# DS2408_2PIO_6S_v2.net
KiCad netlist of a schematic drawn in EAGLE
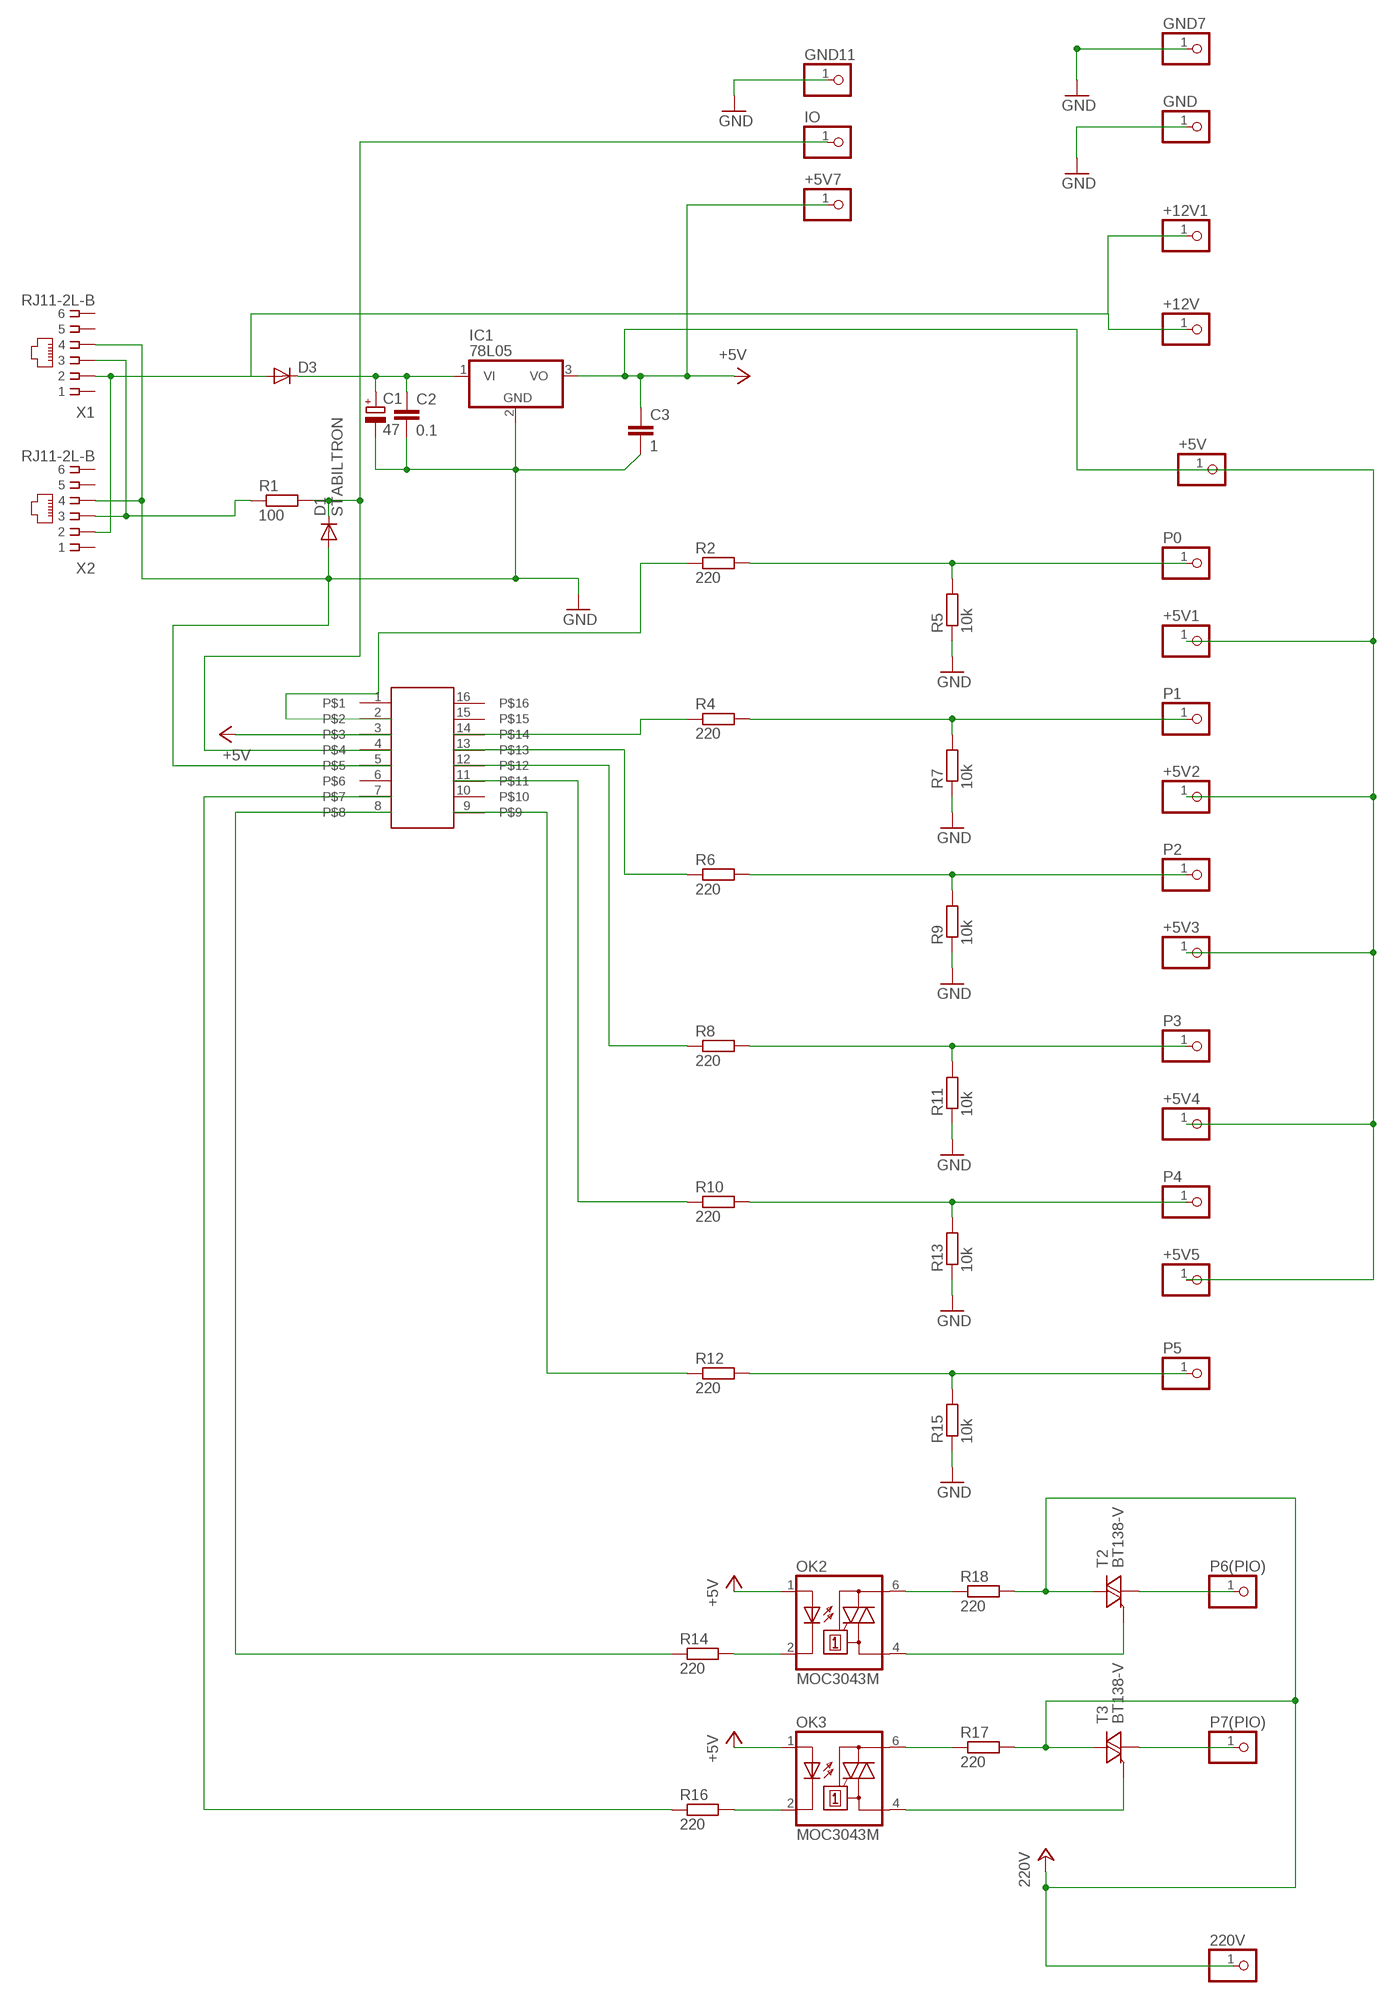
[diagram p0: schematic, sheet 1]

(export (version "E")
  (design (tool "Eeschema 10.0.6"))
  (components
    (comp (ref "+5V")
      (value "PINHD-1X1")
      (footprint "eagle-import:1X01")
      (libsource (lib "eagle-import") (part "PINHD-1X1"))
    )
    (comp (ref "+5V1")
      (value "PINHD-1X1")
      (footprint "eagle-import:1X01")
      (libsource (lib "eagle-import") (part "PINHD-1X1"))
    )
    (comp (ref "+5V2")
      (value "PINHD-1X1")
      (footprint "eagle-import:1X01")
      (libsource (lib "eagle-import") (part "PINHD-1X1"))
    )
    (comp (ref "+5V3")
      (value "PINHD-1X1")
      (footprint "eagle-import:1X01")
      (libsource (lib "eagle-import") (part "PINHD-1X1"))
    )
    (comp (ref "+5V4")
      (value "PINHD-1X1")
      (footprint "eagle-import:1X01")
      (libsource (lib "eagle-import") (part "PINHD-1X1"))
    )
    (comp (ref "+5V5")
      (value "PINHD-1X1")
      (footprint "eagle-import:1X01")
      (libsource (lib "eagle-import") (part "PINHD-1X1"))
    )
    (comp (ref "+5V7")
      (value "PINHD-1X1")
      (footprint "eagle-import:1X01")
      (libsource (lib "eagle-import") (part "PINHD-1X1"))
    )
    (comp (ref "+12V")
      (value "PINHD-1X1")
      (footprint "eagle-import:1X01")
      (libsource (lib "eagle-import") (part "PINHD-1X1"))
    )
    (comp (ref "+12V1")
      (value "PINHD-1X1")
      (footprint "eagle-import:1X01")
      (libsource (lib "eagle-import") (part "PINHD-1X1"))
    )
    (comp (ref "220V")
      (value "PINHD-1X1")
      (footprint "eagle-import:1X01")
      (libsource (lib "eagle-import") (part "PINHD-1X1"))
    )
    (comp (ref "C1")
      (value "47")
      (footprint "eagle-import:E5-10,5")
      (libsource (lib "eagle-import") (part "CPOL-EUE5-10.5"))
    )
    (comp (ref "C2")
      (value "0.1")
      (footprint "eagle-import:C1206")
      (libsource (lib "eagle-import") (part "C-EUC1206"))
    )
    (comp (ref "C3")
      (value "1")
      (footprint "eagle-import:C1206")
      (libsource (lib "eagle-import") (part "C-EUC1206"))
    )
    (comp (ref "D1")
      (value "STABILTRON")
      (footprint "eagle-import:DO35-10")
      (libsource (lib "eagle-import") (part "1N4148DO35-10"))
    )
    (comp (ref "D3")
      (value "DIODE-MINIMELF")
      (footprint "eagle-import:MINIMELF")
      (libsource (lib "eagle-import") (part "DIODE-MINIMELF"))
    )
    (comp (ref "GND")
      (value "PINHD-1X1")
      (footprint "eagle-import:1X01")
      (libsource (lib "eagle-import") (part "PINHD-1X1"))
    )
    (comp (ref "GND7")
      (value "PINHD-1X1")
      (footprint "eagle-import:1X01")
      (libsource (lib "eagle-import") (part "PINHD-1X1"))
    )
    (comp (ref "GND11")
      (value "PINHD-1X1")
      (footprint "eagle-import:1X01")
      (libsource (lib "eagle-import") (part "PINHD-1X1"))
    )
    (comp (ref "IC1")
      (value "78L05")
      (footprint "eagle-import:TO220V")
      (libsource (lib "eagle-import") (part "78TV05"))
    )
    (comp (ref "IO")
      (value "PINHD-1X1")
      (footprint "eagle-import:1X01")
      (libsource (lib "eagle-import") (part "PINHD-1X1"))
    )
    (comp (ref "OK2")
      (value "MOC3043M")
      (footprint "eagle-import:DIL06")
      (fields (field (name "MF") "FAIRCHILD SEMICONDUCTOR") (field (name "MPN") "MOC3043-M"))
      (libsource (lib "eagle-import") (part "MOC3043M"))
    )
    (comp (ref "OK3")
      (value "MOC3043M")
      (footprint "eagle-import:DIL06")
      (fields (field (name "MF") "FAIRCHILD SEMICONDUCTOR") (field (name "MPN") "MOC3043-M"))
      (libsource (lib "eagle-import") (part "MOC3043M"))
    )
    (comp (ref "P0")
      (value "PINHD-1X1")
      (footprint "eagle-import:1X01")
      (libsource (lib "eagle-import") (part "PINHD-1X1"))
    )
    (comp (ref "P1")
      (value "PINHD-1X1")
      (footprint "eagle-import:1X01")
      (libsource (lib "eagle-import") (part "PINHD-1X1"))
    )
    (comp (ref "P2")
      (value "PINHD-1X1")
      (footprint "eagle-import:1X01")
      (libsource (lib "eagle-import") (part "PINHD-1X1"))
    )
    (comp (ref "P3")
      (value "PINHD-1X1")
      (footprint "eagle-import:1X01")
      (libsource (lib "eagle-import") (part "PINHD-1X1"))
    )
    (comp (ref "P4")
      (value "PINHD-1X1")
      (footprint "eagle-import:1X01")
      (libsource (lib "eagle-import") (part "PINHD-1X1"))
    )
    (comp (ref "P5")
      (value "PINHD-1X1")
      (footprint "eagle-import:1X01")
      (libsource (lib "eagle-import") (part "PINHD-1X1"))
    )
    (comp (ref "P6(PIO)")
      (value "PINHD-1X1")
      (footprint "eagle-import:1X01")
      (libsource (lib "eagle-import") (part "PINHD-1X1"))
    )
    (comp (ref "P7(PIO)")
      (value "PINHD-1X1")
      (footprint "eagle-import:1X01")
      (libsource (lib "eagle-import") (part "PINHD-1X1"))
    )
    (comp (ref "R1")
      (value "100")
      (footprint "eagle-import:M1206")
      (libsource (lib "eagle-import") (part "R-EU_M1206"))
    )
    (comp (ref "R2")
      (value "220")
      (footprint "eagle-import:M1206")
      (libsource (lib "eagle-import") (part "R-EU_M1206"))
    )
    (comp (ref "R4")
      (value "220")
      (footprint "eagle-import:M1206")
      (libsource (lib "eagle-import") (part "R-EU_M1206"))
    )
    (comp (ref "R5")
      (value "10k")
      (footprint "eagle-import:M1206")
      (libsource (lib "eagle-import") (part "R-EU_M1206"))
    )
    (comp (ref "R6")
      (value "220")
      (footprint "eagle-import:M1206")
      (libsource (lib "eagle-import") (part "R-EU_M1206"))
    )
    (comp (ref "R7")
      (value "10k")
      (footprint "eagle-import:M1206")
      (libsource (lib "eagle-import") (part "R-EU_M1206"))
    )
    (comp (ref "R8")
      (value "220")
      (footprint "eagle-import:M1206")
      (libsource (lib "eagle-import") (part "R-EU_M1206"))
    )
    (comp (ref "R9")
      (value "10k")
      (footprint "eagle-import:M1206")
      (libsource (lib "eagle-import") (part "R-EU_M1206"))
    )
    (comp (ref "R10")
      (value "220")
      (footprint "eagle-import:M1206")
      (libsource (lib "eagle-import") (part "R-EU_M1206"))
    )
    (comp (ref "R11")
      (value "10k")
      (footprint "eagle-import:M1206")
      (libsource (lib "eagle-import") (part "R-EU_M1206"))
    )
    (comp (ref "R12")
      (value "220")
      (footprint "eagle-import:M1206")
      (libsource (lib "eagle-import") (part "R-EU_M1206"))
    )
    (comp (ref "R13")
      (value "10k")
      (footprint "eagle-import:M1206")
      (libsource (lib "eagle-import") (part "R-EU_M1206"))
    )
    (comp (ref "R14")
      (value "220")
      (footprint "eagle-import:M1206")
      (libsource (lib "eagle-import") (part "R-EU_M1206"))
    )
    (comp (ref "R15")
      (value "10k")
      (footprint "eagle-import:M1206")
      (libsource (lib "eagle-import") (part "R-EU_M1206"))
    )
    (comp (ref "R16")
      (value "220")
      (footprint "eagle-import:M1206")
      (libsource (lib "eagle-import") (part "R-EU_M1206"))
    )
    (comp (ref "R17")
      (value "220")
      (footprint "eagle-import:M1206")
      (libsource (lib "eagle-import") (part "R-EU_M1206"))
    )
    (comp (ref "R18")
      (value "220")
      (footprint "eagle-import:M1206")
      (libsource (lib "eagle-import") (part "R-EU_M1206"))
    )
    (comp (ref "T2")
      (value "BT138-V")
      (footprint "eagle-import:TO220BV")
      (libsource (lib "eagle-import") (part "BT138-V"))
    )
    (comp (ref "T3")
      (value "BT138-V")
      (footprint "eagle-import:TO220BV")
      (libsource (lib "eagle-import") (part "BT138-V"))
    )
    (comp (ref "U$1")
      (value "DS2408S")
      (footprint "eagle-import:SO16")
      (libsource (lib "eagle-import") (part "DS2408S"))
    )
    (comp (ref "X1")
      (value "RJ11-2L-B")
      (footprint "eagle-import:RJ11-NO_SHIELD")
      (fields (field (name "MF") "TYCO ELECTRONICS"))
      (libsource (lib "eagle-import") (part "RJ11-2L-B"))
    )
    (comp (ref "X2")
      (value "RJ11-2L-B")
      (footprint "eagle-import:RJ11-NO_SHIELD")
      (fields (field (name "MF") "TYCO ELECTRONICS"))
      (libsource (lib "eagle-import") (part "RJ11-2L-B"))
    )
  )
  (nets
    (net (code "1") (name "+5V") (class "Default")
      (node (ref "+5V") (pin "1") (pinfunction "1_1") (pintype "passive"))
      (node (ref "+5V1") (pin "1") (pinfunction "1_1") (pintype "passive"))
      (node (ref "+5V2") (pin "1") (pinfunction "1_1") (pintype "passive"))
      (node (ref "+5V3") (pin "1") (pinfunction "1_1") (pintype "passive"))
      (node (ref "+5V4") (pin "1") (pinfunction "1_1") (pintype "passive"))
      (node (ref "+5V5") (pin "1") (pinfunction "1_1") (pintype "passive"))
      (node (ref "+5V7") (pin "1") (pinfunction "1_1") (pintype "passive"))
      (node (ref "C3") (pin "1") (pinfunction "1_1") (pintype "passive"))
      (node (ref "IC1") (pin "3") (pinfunction "VO_3") (pintype "passive"))
      (node (ref "OK2") (pin "1") (pinfunction "A_1") (pintype "passive"))
      (node (ref "OK3") (pin "1") (pinfunction "A_1") (pintype "passive"))
      (node (ref "U$1") (pin "3") (pinfunction "P$3_3") (pintype "bidirectional"))
    )
    (net (code "2") (name "220V") (class "Default")
      (node (ref "220V") (pin "1") (pinfunction "1_1") (pintype "passive"))
      (node (ref "R17") (pin "2") (pinfunction "2_2") (pintype "passive"))
      (node (ref "R18") (pin "2") (pinfunction "2_2") (pintype "passive"))
      (node (ref "T2") (pin "T2") (pinfunction "A2_T2") (pintype "passive"))
      (node (ref "T3") (pin "T2") (pinfunction "A2_T2") (pintype "passive"))
    )
    (net (code "3") (name "GND") (class "Default")
      (node (ref "C1") (pin "-") (pinfunction "-_-") (pintype "passive"))
      (node (ref "C2") (pin "2") (pinfunction "2_2") (pintype "passive"))
      (node (ref "C3") (pin "2") (pinfunction "2_2") (pintype "passive"))
      (node (ref "D1") (pin "A") (pinfunction "A_A") (pintype "passive"))
      (node (ref "GND") (pin "1") (pinfunction "1_1") (pintype "passive"))
      (node (ref "GND11") (pin "1") (pinfunction "1_1") (pintype "passive"))
      (node (ref "GND7") (pin "1") (pinfunction "1_1") (pintype "passive"))
      (node (ref "IC1") (pin "2") (pinfunction "GND_2") (pintype "passive"))
      (node (ref "R11") (pin "1") (pinfunction "1_1") (pintype "passive"))
      (node (ref "R13") (pin "1") (pinfunction "1_1") (pintype "passive"))
      (node (ref "R15") (pin "1") (pinfunction "1_1") (pintype "passive"))
      (node (ref "R5") (pin "1") (pinfunction "1_1") (pintype "passive"))
      (node (ref "R7") (pin "1") (pinfunction "1_1") (pintype "passive"))
      (node (ref "R9") (pin "1") (pinfunction "1_1") (pintype "passive"))
      (node (ref "U$1") (pin "5") (pinfunction "P$5_5") (pintype "bidirectional"))
      (node (ref "X1") (pin "4") (pinfunction "4_4") (pintype "passive"))
      (node (ref "X2") (pin "4") (pinfunction "4_4") (pintype "passive"))
    )
    (net (code "4") (name "Net-(+12V-Pad1)") (class "Default")
      (node (ref "+12V") (pin "1") (pinfunction "1_1") (pintype "passive"))
      (node (ref "+12V1") (pin "1") (pinfunction "1_1") (pintype "passive"))
      (node (ref "D3") (pin "A") (pinfunction "A_A") (pintype "passive"))
      (node (ref "X1") (pin "2") (pinfunction "2_2") (pintype "passive"))
      (node (ref "X2") (pin "2") (pinfunction "2_2") (pintype "passive"))
    )
    (net (code "5") (name "Net-(IC1-VI)") (class "Default")
      (node (ref "C1") (pin "+") (pinfunction "+_+") (pintype "passive"))
      (node (ref "C2") (pin "1") (pinfunction "1_1") (pintype "passive"))
      (node (ref "D3") (pin "C") (pinfunction "C_C") (pintype "passive"))
      (node (ref "IC1") (pin "1") (pinfunction "VI_1") (pintype "input"))
    )
    (net (code "6") (name "Net-(OK2-A1)") (class "Default")
      (node (ref "OK2") (pin "4") (pinfunction "A1_4") (pintype "passive"))
      (node (ref "T2") (pin "G") (pinfunction "G_G") (pintype "passive"))
    )
    (net (code "7") (name "Net-(OK2-A2)") (class "Default")
      (node (ref "OK2") (pin "6") (pinfunction "A2_6") (pintype "passive"))
      (node (ref "R18") (pin "1") (pinfunction "1_1") (pintype "passive"))
    )
    (net (code "8") (name "Net-(OK2-C)") (class "Default")
      (node (ref "OK2") (pin "2") (pinfunction "C_2") (pintype "passive"))
      (node (ref "R14") (pin "2") (pinfunction "2_2") (pintype "passive"))
    )
    (net (code "9") (name "Net-(OK3-A1)") (class "Default")
      (node (ref "OK3") (pin "4") (pinfunction "A1_4") (pintype "passive"))
      (node (ref "T3") (pin "G") (pinfunction "G_G") (pintype "passive"))
    )
    (net (code "10") (name "Net-(OK3-A2)") (class "Default")
      (node (ref "OK3") (pin "6") (pinfunction "A2_6") (pintype "passive"))
      (node (ref "R17") (pin "1") (pinfunction "1_1") (pintype "passive"))
    )
    (net (code "11") (name "Net-(OK3-C)") (class "Default")
      (node (ref "OK3") (pin "2") (pinfunction "C_2") (pintype "passive"))
      (node (ref "R16") (pin "2") (pinfunction "2_2") (pintype "passive"))
    )
    (net (code "12") (name "Net-(P0-Pad1)") (class "Default")
      (node (ref "P0") (pin "1") (pinfunction "1_1") (pintype "passive"))
      (node (ref "R2") (pin "2") (pinfunction "2_2") (pintype "passive"))
      (node (ref "R5") (pin "2") (pinfunction "2_2") (pintype "passive"))
    )
    (net (code "13") (name "Net-(P1-Pad1)") (class "Default")
      (node (ref "P1") (pin "1") (pinfunction "1_1") (pintype "passive"))
      (node (ref "R4") (pin "2") (pinfunction "2_2") (pintype "passive"))
      (node (ref "R7") (pin "2") (pinfunction "2_2") (pintype "passive"))
    )
    (net (code "14") (name "Net-(P2-Pad1)") (class "Default")
      (node (ref "P2") (pin "1") (pinfunction "1_1") (pintype "passive"))
      (node (ref "R6") (pin "2") (pinfunction "2_2") (pintype "passive"))
      (node (ref "R9") (pin "2") (pinfunction "2_2") (pintype "passive"))
    )
    (net (code "15") (name "Net-(P3-Pad1)") (class "Default")
      (node (ref "P3") (pin "1") (pinfunction "1_1") (pintype "passive"))
      (node (ref "R11") (pin "2") (pinfunction "2_2") (pintype "passive"))
      (node (ref "R8") (pin "2") (pinfunction "2_2") (pintype "passive"))
    )
    (net (code "16") (name "Net-(P4-Pad1)") (class "Default")
      (node (ref "P4") (pin "1") (pinfunction "1_1") (pintype "passive"))
      (node (ref "R10") (pin "2") (pinfunction "2_2") (pintype "passive"))
      (node (ref "R13") (pin "2") (pinfunction "2_2") (pintype "passive"))
    )
    (net (code "17") (name "Net-(P5-Pad1)") (class "Default")
      (node (ref "P5") (pin "1") (pinfunction "1_1") (pintype "passive"))
      (node (ref "R12") (pin "2") (pinfunction "2_2") (pintype "passive"))
      (node (ref "R15") (pin "2") (pinfunction "2_2") (pintype "passive"))
    )
    (net (code "18") (name "Net-(R1-Pad1)") (class "Default")
      (node (ref "R1") (pin "1") (pinfunction "1_1") (pintype "passive"))
      (node (ref "X1") (pin "3") (pinfunction "3_3") (pintype "passive"))
      (node (ref "X2") (pin "3") (pinfunction "3_3") (pintype "passive"))
    )
    (net (code "19") (name "Net-(T2-A1)") (class "Default")
      (node (ref "P6(PIO)") (pin "1") (pinfunction "1_1") (pintype "passive"))
      (node (ref "T2") (pin "T1") (pinfunction "A1_T1") (pintype "passive"))
    )
    (net (code "20") (name "Net-(T3-A1)") (class "Default")
      (node (ref "P7(PIO)") (pin "1") (pinfunction "1_1") (pintype "passive"))
      (node (ref "T3") (pin "T1") (pinfunction "A1_T1") (pintype "passive"))
    )
    (net (code "21") (name "Net-(U$1-P$2)") (class "Default")
      (node (ref "R2") (pin "1") (pinfunction "1_1") (pintype "passive"))
      (node (ref "U$1") (pin "2") (pinfunction "P$2_2") (pintype "bidirectional"))
    )
    (net (code "22") (name "Net-(U$1-P$4)") (class "Default")
      (node (ref "D1") (pin "C") (pinfunction "C_C") (pintype "passive"))
      (node (ref "IO") (pin "1") (pinfunction "1_1") (pintype "passive"))
      (node (ref "R1") (pin "2") (pinfunction "2_2") (pintype "passive"))
      (node (ref "U$1") (pin "4") (pinfunction "P$4_4") (pintype "bidirectional"))
    )
    (net (code "23") (name "Net-(U$1-P$7)") (class "Default")
      (node (ref "R16") (pin "1") (pinfunction "1_1") (pintype "passive"))
      (node (ref "U$1") (pin "7") (pinfunction "P$7_7") (pintype "bidirectional"))
    )
    (net (code "24") (name "Net-(U$1-P$8)") (class "Default")
      (node (ref "R14") (pin "1") (pinfunction "1_1") (pintype "passive"))
      (node (ref "U$1") (pin "8") (pinfunction "P$8_8") (pintype "bidirectional"))
    )
    (net (code "25") (name "Net-(U$1-P$9)") (class "Default")
      (node (ref "R12") (pin "1") (pinfunction "1_1") (pintype "passive"))
      (node (ref "U$1") (pin "9") (pinfunction "P$9_9") (pintype "bidirectional"))
    )
    (net (code "26") (name "Net-(U$1-P$11)") (class "Default")
      (node (ref "R10") (pin "1") (pinfunction "1_1") (pintype "passive"))
      (node (ref "U$1") (pin "11") (pinfunction "P$11_11") (pintype "bidirectional"))
    )
    (net (code "27") (name "Net-(U$1-P$12)") (class "Default")
      (node (ref "R8") (pin "1") (pinfunction "1_1") (pintype "passive"))
      (node (ref "U$1") (pin "12") (pinfunction "P$12_12") (pintype "bidirectional"))
    )
    (net (code "28") (name "Net-(U$1-P$13)") (class "Default")
      (node (ref "R6") (pin "1") (pinfunction "1_1") (pintype "passive"))
      (node (ref "U$1") (pin "13") (pinfunction "P$13_13") (pintype "bidirectional"))
    )
    (net (code "29") (name "Net-(U$1-P$14)") (class "Default")
      (node (ref "R4") (pin "1") (pinfunction "1_1") (pintype "passive"))
      (node (ref "U$1") (pin "14") (pinfunction "P$14_14") (pintype "bidirectional"))
    )
    (net (code "30") (name "unconnected-(U$1-P$1-Pad1)") (class "Default")
      (node (ref "U$1") (pin "1") (pinfunction "P$1_1") (pintype "bidirectional"))
    )
    (net (code "31") (name "unconnected-(U$1-P$6-Pad6)") (class "Default")
      (node (ref "U$1") (pin "6") (pinfunction "P$6_6") (pintype "bidirectional"))
    )
    (net (code "32") (name "unconnected-(U$1-P$10-Pad10)") (class "Default")
      (node (ref "U$1") (pin "10") (pinfunction "P$10_10") (pintype "bidirectional"))
    )
    (net (code "33") (name "unconnected-(U$1-P$15-Pad15)") (class "Default")
      (node (ref "U$1") (pin "15") (pinfunction "P$15_15") (pintype "bidirectional"))
    )
    (net (code "34") (name "unconnected-(U$1-P$16-Pad16)") (class "Default")
      (node (ref "U$1") (pin "16") (pinfunction "P$16_16") (pintype "bidirectional"))
    )
    (net (code "35") (name "unconnected-(X1-Pad1)") (class "Default")
      (node (ref "X1") (pin "1") (pinfunction "1_1") (pintype "passive"))
    )
    (net (code "36") (name "unconnected-(X1-Pad5)") (class "Default")
      (node (ref "X1") (pin "5") (pinfunction "5_5") (pintype "passive"))
    )
    (net (code "37") (name "unconnected-(X1-Pad6)") (class "Default")
      (node (ref "X1") (pin "6") (pinfunction "6_6") (pintype "passive"))
    )
    (net (code "38") (name "unconnected-(X2-Pad1)") (class "Default")
      (node (ref "X2") (pin "1") (pinfunction "1_1") (pintype "passive"))
    )
    (net (code "39") (name "unconnected-(X2-Pad5)") (class "Default")
      (node (ref "X2") (pin "5") (pinfunction "5_5") (pintype "passive"))
    )
    (net (code "40") (name "unconnected-(X2-Pad6)") (class "Default")
      (node (ref "X2") (pin "6") (pinfunction "6_6") (pintype "passive"))
    )
  )
)
